# V2_3.net
KiCad netlist of a schematic drawn in Altium Designer
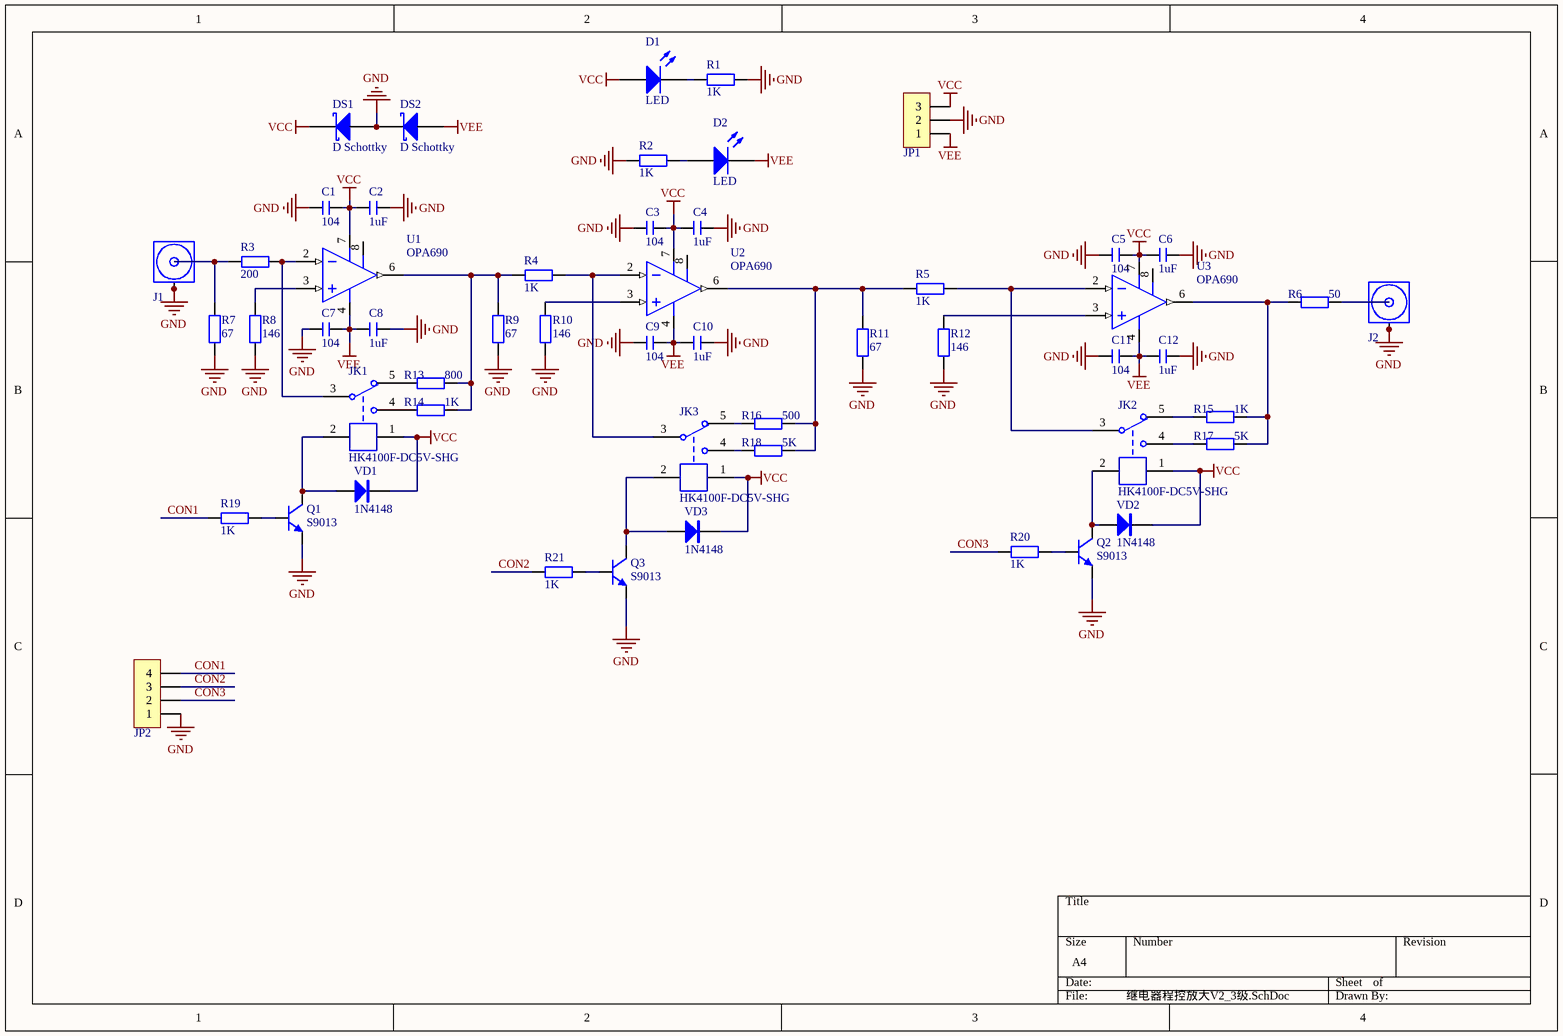
[diagram p0: 继电器程控放大V2_3级.SchDoc]

(export (version "E")
  (design (tool "Eeschema 10.0.6"))
  (components
    (comp (ref "C1")
      (value "104")
      (footprint "C 0603")
      (description "无极性贴片电容")
      (fields (field (name "版权归属") "源创客"))
      (libsource (lib "电阻-电容-电感") (part "C"))
    )
    (comp (ref "C2")
      (value "1uF")
      (footprint "C 0603")
      (description "无极性贴片电容")
      (fields (field (name "版权归属") "源创客"))
      (libsource (lib "电阻-电容-电感") (part "C"))
    )
    (comp (ref "C3")
      (value "104")
      (footprint "C 0603")
      (description "无极性贴片电容")
      (fields (field (name "版权归属") "源创客"))
      (libsource (lib "电阻-电容-电感") (part "C"))
    )
    (comp (ref "C4")
      (value "1uF")
      (footprint "C 0603")
      (description "无极性贴片电容")
      (fields (field (name "版权归属") "源创客"))
      (libsource (lib "电阻-电容-电感") (part "C"))
    )
    (comp (ref "C5")
      (value "104")
      (footprint "C 0603")
      (description "无极性贴片电容")
      (fields (field (name "版权归属") "源创客"))
      (libsource (lib "电阻-电容-电感") (part "C"))
    )
    (comp (ref "C6")
      (value "1uF")
      (footprint "C 0603")
      (description "无极性贴片电容")
      (fields (field (name "版权归属") "源创客"))
      (libsource (lib "电阻-电容-电感") (part "C"))
    )
    (comp (ref "C7")
      (value "104")
      (footprint "C 0603")
      (description "无极性贴片电容")
      (fields (field (name "版权归属") "源创客"))
      (libsource (lib "电阻-电容-电感") (part "C"))
    )
    (comp (ref "C8")
      (value "1uF")
      (footprint "C 0603")
      (description "无极性贴片电容")
      (fields (field (name "版权归属") "源创客"))
      (libsource (lib "电阻-电容-电感") (part "C"))
    )
    (comp (ref "C9")
      (value "104")
      (footprint "C 0603")
      (description "无极性贴片电容")
      (fields (field (name "版权归属") "源创客"))
      (libsource (lib "电阻-电容-电感") (part "C"))
    )
    (comp (ref "C10")
      (value "1uF")
      (footprint "C 0603")
      (description "无极性贴片电容")
      (fields (field (name "版权归属") "源创客"))
      (libsource (lib "电阻-电容-电感") (part "C"))
    )
    (comp (ref "C11")
      (value "104")
      (footprint "C 0603")
      (description "无极性贴片电容")
      (fields (field (name "版权归属") "源创客"))
      (libsource (lib "电阻-电容-电感") (part "C"))
    )
    (comp (ref "C12")
      (value "1uF")
      (footprint "C 0603")
      (description "无极性贴片电容")
      (fields (field (name "版权归属") "源创客"))
      (libsource (lib "电阻-电容-电感") (part "C"))
    )
    (comp (ref "D1")
      (value "LED")
      (footprint "LED_0805")
      (description "发光二极管")
      (fields (field (name "PUBLISHER") "Altium Limited"))
      (libsource (lib "LIB") (part "LED"))
    )
    (comp (ref "D2")
      (value "LED")
      (footprint "LED_0805")
      (description "发光二极管")
      (fields (field (name "PUBLISHER") "Altium Limited"))
      (libsource (lib "LIB") (part "LED"))
    )
    (comp (ref "DS1")
      (value "D Schottky")
      (footprint "DIODE-SMA")
      (description "Schottky Diode")
      (fields (field (name "PUBLISHER") "Altium Limited"))
      (libsource (lib "LIB") (part "D Schottky"))
    )
    (comp (ref "DS2")
      (value "D Schottky")
      (footprint "DIODE-SMA")
      (description "Schottky Diode")
      (fields (field (name "PUBLISHER") "Altium Limited"))
      (libsource (lib "LIB") (part "D Schottky"))
    )
    (comp (ref "J1") (value "COAX") (footprint "MCX5.08-5-H") (libsource (lib "LIB") (part "COAX")))
    (comp (ref "J2") (value "COAX") (footprint "MCX5.08-5-H") (libsource (lib "LIB") (part "COAX")))
    (comp (ref "JK1")
      (value "HK4100F-DC5V-SHG")
      (footprint "HK4100F")
      (description "单路双控继电器")
      (fields (field (name "版权归属") "源创客"))
      (libsource (lib "继电器") (part "HK4100F"))
    )
    (comp (ref "JK2")
      (value "HK4100F-DC5V-SHG")
      (footprint "HK4100F")
      (description "单路双控继电器")
      (fields (field (name "版权归属") "源创客"))
      (libsource (lib "继电器") (part "HK4100F"))
    )
    (comp (ref "JK3")
      (value "HK4100F-DC5V-SHG")
      (footprint "HK4100F")
      (description "单路双控继电器")
      (fields (field (name "版权归属") "源创客"))
      (libsource (lib "继电器") (part "HK4100F"))
    )
    (comp (ref "JP1")
      (value "HDR-1X3")
      (footprint "XH2.54-3P_H")
      (description "3P接插件")
      (fields (field (name "版权归属") "源创客"))
      (libsource (lib "接插件") (part "Header 3"))
    )
    (comp (ref "JP2")
      (value "HDR-1X4")
      (footprint "HDR-1X4")
      (description "4P接插件")
      (fields (field (name "版权归属") "源创客"))
      (libsource (lib "接插件") (part "Header 4"))
    )
    (comp (ref "Q1")
      (value "S9013")
      (footprint "SOT23-3N")
      (description "低频放大-NPN型")
      (fields (field (name "版权归属") "源创客"))
      (libsource (lib "三极管") (part "9013-SMD"))
    )
    (comp (ref "Q2")
      (value "S9013")
      (footprint "SOT23-3N")
      (description "低频放大-NPN型")
      (fields (field (name "版权归属") "源创客"))
      (libsource (lib "三极管") (part "9013-SMD"))
    )
    (comp (ref "Q3")
      (value "S9013")
      (footprint "SOT23-3N")
      (description "低频放大-NPN型")
      (fields (field (name "版权归属") "源创客"))
      (libsource (lib "三极管") (part "9013-SMD"))
    )
    (comp (ref "R1")
      (value "1K")
      (footprint "R 0805")
      (description "贴片电阻")
      (fields (field (name "版权归属") "源创客"))
      (libsource (lib "电阻-电容-电感") (part "R"))
    )
    (comp (ref "R2")
      (value "1K")
      (footprint "R 0805")
      (description "贴片电阻")
      (fields (field (name "版权归属") "源创客"))
      (libsource (lib "电阻-电容-电感") (part "R"))
    )
    (comp (ref "R3")
      (value "200")
      (footprint "R 0603")
      (description "贴片电阻")
      (fields (field (name "版权归属") "源创客"))
      (libsource (lib "电阻-电容-电感") (part "R"))
    )
    (comp (ref "R4")
      (value "1K")
      (footprint "R 0603")
      (description "贴片电阻")
      (fields (field (name "版权归属") "源创客"))
      (libsource (lib "电阻-电容-电感") (part "R"))
    )
    (comp (ref "R5")
      (value "1K")
      (footprint "R 0603")
      (description "贴片电阻")
      (fields (field (name "版权归属") "源创客"))
      (libsource (lib "电阻-电容-电感") (part "R"))
    )
    (comp (ref "R6")
      (value "50")
      (footprint "R 0603")
      (description "贴片电阻")
      (fields (field (name "版权归属") "源创客"))
      (libsource (lib "电阻-电容-电感") (part "R"))
    )
    (comp (ref "R7")
      (value "67")
      (footprint "R 0603")
      (description "贴片电阻")
      (fields (field (name "版权归属") "源创客"))
      (libsource (lib "电阻-电容-电感") (part "R"))
    )
    (comp (ref "R8")
      (value "146")
      (footprint "R 0603")
      (description "贴片电阻")
      (fields (field (name "版权归属") "源创客"))
      (libsource (lib "电阻-电容-电感") (part "R"))
    )
    (comp (ref "R9")
      (value "67")
      (footprint "R 0603")
      (description "贴片电阻")
      (fields (field (name "版权归属") "源创客"))
      (libsource (lib "电阻-电容-电感") (part "R"))
    )
    (comp (ref "R10")
      (value "146")
      (footprint "R 0603")
      (description "贴片电阻")
      (fields (field (name "版权归属") "源创客"))
      (libsource (lib "电阻-电容-电感") (part "R"))
    )
    (comp (ref "R11")
      (value "67")
      (footprint "R 0603")
      (description "贴片电阻")
      (fields (field (name "版权归属") "源创客"))
      (libsource (lib "电阻-电容-电感") (part "R"))
    )
    (comp (ref "R12")
      (value "146")
      (footprint "R 0603")
      (description "贴片电阻")
      (fields (field (name "版权归属") "源创客"))
      (libsource (lib "电阻-电容-电感") (part "R"))
    )
    (comp (ref "R13")
      (value "800")
      (footprint "R 0603")
      (description "贴片电阻")
      (fields (field (name "版权归属") "源创客"))
      (libsource (lib "电阻-电容-电感") (part "R"))
    )
    (comp (ref "R14")
      (value "1K")
      (footprint "R 0603")
      (description "贴片电阻")
      (fields (field (name "版权归属") "源创客"))
      (libsource (lib "电阻-电容-电感") (part "R"))
    )
    (comp (ref "R15")
      (value "1K")
      (footprint "R 0603")
      (description "贴片电阻")
      (fields (field (name "版权归属") "源创客"))
      (libsource (lib "电阻-电容-电感") (part "R"))
    )
    (comp (ref "R16")
      (value "500")
      (footprint "R 0603")
      (description "贴片电阻")
      (fields (field (name "版权归属") "源创客"))
      (libsource (lib "电阻-电容-电感") (part "R"))
    )
    (comp (ref "R17")
      (value "5K")
      (footprint "R 0603")
      (description "贴片电阻")
      (fields (field (name "版权归属") "源创客"))
      (libsource (lib "电阻-电容-电感") (part "R"))
    )
    (comp (ref "R18")
      (value "5K")
      (footprint "R 0603")
      (description "贴片电阻")
      (fields (field (name "版权归属") "源创客"))
      (libsource (lib "电阻-电容-电感") (part "R"))
    )
    (comp (ref "R19")
      (value "1K")
      (footprint "R 0603")
      (description "贴片电阻")
      (fields (field (name "版权归属") "源创客"))
      (libsource (lib "电阻-电容-电感") (part "R"))
    )
    (comp (ref "R20")
      (value "1K")
      (footprint "R 0603")
      (description "贴片电阻")
      (fields (field (name "版权归属") "源创客"))
      (libsource (lib "电阻-电容-电感") (part "R"))
    )
    (comp (ref "R21")
      (value "1K")
      (footprint "R 0603")
      (description "贴片电阻")
      (fields (field (name "版权归属") "源创客"))
      (libsource (lib "电阻-电容-电感") (part "R"))
    )
    (comp (ref "U1")
      (value "OPA690")
      (footprint "LIB:SOIC8_N")
      (description "具有禁用功能的宽带电压反馈运算放大器")
      (libsource (lib "LIB") (part "OPA690ID"))
    )
    (comp (ref "U2")
      (value "OPA690")
      (footprint "LIB:SOIC8_N")
      (description "具有禁用功能的宽带电压反馈运算放大器")
      (libsource (lib "LIB") (part "OPA690ID"))
    )
    (comp (ref "U3")
      (value "OPA690")
      (footprint "LIB:SOIC8_N")
      (description "具有禁用功能的宽带电压反馈运算放大器")
      (libsource (lib "LIB") (part "OPA690ID"))
    )
    (comp (ref "VD1")
      (value "1N4148")
      (footprint "SOD-323")
      (description "高速开关二极管")
      (fields (field (name "版权归属") "源创客"))
      (libsource (lib "二极管-整流桥") (part "1N4148"))
    )
    (comp (ref "VD2")
      (value "1N4148")
      (footprint "SOD-323")
      (description "高速开关二极管")
      (fields (field (name "版权归属") "源创客"))
      (libsource (lib "二极管-整流桥") (part "1N4148"))
    )
    (comp (ref "VD3")
      (value "1N4148")
      (footprint "SOD-323")
      (description "高速开关二极管")
      (fields (field (name "版权归属") "源创客"))
      (libsource (lib "二极管-整流桥") (part "1N4148"))
    )
  )
  (nets
    (net (code "1") (name "/CON1") (class "Default")
      (node (ref "JP2") (pin "4") (pinfunction "4_4") (pintype "passive"))
      (node (ref "R19") (pin "1") (pinfunction "1_1") (pintype "passive"))
    )
    (net (code "2") (name "/CON2") (class "Default")
      (node (ref "JP2") (pin "3") (pinfunction "3_3") (pintype "passive"))
      (node (ref "R21") (pin "1") (pinfunction "1_1") (pintype "passive"))
    )
    (net (code "3") (name "/CON3") (class "Default")
      (node (ref "JP2") (pin "2") (pinfunction "2_2") (pintype "passive"))
      (node (ref "R20") (pin "1") (pinfunction "1_1") (pintype "passive"))
    )
    (net (code "4") (name "GND") (class "Default")
      (node (ref "C1") (pin "1") (pinfunction "1_1") (pintype "passive"))
      (node (ref "C10") (pin "2") (pinfunction "2_2") (pintype "passive"))
      (node (ref "C11") (pin "1") (pinfunction "1_1") (pintype "passive"))
      (node (ref "C12") (pin "2") (pinfunction "2_2") (pintype "passive"))
      (node (ref "C2") (pin "2") (pinfunction "2_2") (pintype "passive"))
      (node (ref "C3") (pin "1") (pinfunction "1_1") (pintype "passive"))
      (node (ref "C4") (pin "2") (pinfunction "2_2") (pintype "passive"))
      (node (ref "C5") (pin "1") (pinfunction "1_1") (pintype "passive"))
      (node (ref "C6") (pin "2") (pinfunction "2_2") (pintype "passive"))
      (node (ref "C7") (pin "1") (pinfunction "1_1") (pintype "passive"))
      (node (ref "C8") (pin "2") (pinfunction "2_2") (pintype "passive"))
      (node (ref "C9") (pin "1") (pinfunction "1_1") (pintype "passive"))
      (node (ref "DS1") (pin "1") (pinfunction "1_1") (pintype "passive"))
      (node (ref "DS2") (pin "2") (pinfunction "2_2") (pintype "passive"))
      (node (ref "J1") (pin "2") (pinfunction "GND_2") (pintype "passive"))
      (node (ref "J1") (pin "3") (pinfunction "GND_3") (pintype "passive"))
      (node (ref "J1") (pin "4") (pinfunction "GND_4") (pintype "passive"))
      (node (ref "J1") (pin "5") (pinfunction "GND_5") (pintype "passive"))
      (node (ref "J2") (pin "2") (pinfunction "GND_2") (pintype "passive"))
      (node (ref "J2") (pin "3") (pinfunction "GND_3") (pintype "passive"))
      (node (ref "J2") (pin "4") (pinfunction "GND_4") (pintype "passive"))
      (node (ref "J2") (pin "5") (pinfunction "GND_5") (pintype "passive"))
      (node (ref "JP1") (pin "2") (pinfunction "2_2") (pintype "passive"))
      (node (ref "JP2") (pin "1") (pinfunction "1_1") (pintype "passive"))
      (node (ref "Q1") (pin "2") (pinfunction "E_2") (pintype "passive"))
      (node (ref "Q2") (pin "2") (pinfunction "E_2") (pintype "passive"))
      (node (ref "Q3") (pin "2") (pinfunction "E_2") (pintype "passive"))
      (node (ref "R1") (pin "2") (pinfunction "2_2") (pintype "passive"))
      (node (ref "R10") (pin "2") (pinfunction "2_2") (pintype "passive"))
      (node (ref "R11") (pin "2") (pinfunction "2_2") (pintype "passive"))
      (node (ref "R12") (pin "2") (pinfunction "2_2") (pintype "passive"))
      (node (ref "R2") (pin "1") (pinfunction "1_1") (pintype "passive"))
      (node (ref "R7") (pin "2") (pinfunction "2_2") (pintype "passive"))
      (node (ref "R8") (pin "1") (pinfunction "1_1") (pintype "passive"))
      (node (ref "R9") (pin "2") (pinfunction "2_2") (pintype "passive"))
    )
    (net (code "5") (name "Net-(D1-K)") (class "Default")
      (node (ref "D1") (pin "2") (pinfunction "K_2") (pintype "passive"))
      (node (ref "R1") (pin "1") (pinfunction "1_1") (pintype "passive"))
    )
    (net (code "6") (name "Net-(D2-A)") (class "Default")
      (node (ref "D2") (pin "1") (pinfunction "A_1") (pintype "passive"))
      (node (ref "R2") (pin "2") (pinfunction "2_2") (pintype "passive"))
    )
    (net (code "7") (name "Net-(J1-Signal)") (class "Default")
      (node (ref "J1") (pin "1") (pinfunction "Signal_1") (pintype "passive"))
      (node (ref "R3") (pin "2") (pinfunction "2_2") (pintype "passive"))
      (node (ref "R7") (pin "1") (pinfunction "1_1") (pintype "passive"))
    )
    (net (code "8") (name "Net-(J2-Signal)") (class "Default")
      (node (ref "J2") (pin "1") (pinfunction "Signal_1") (pintype "passive"))
      (node (ref "R6") (pin "1") (pinfunction "1_1") (pintype "passive"))
    )
    (net (code "9") (name "Net-(JK1-Pad4)") (class "Default")
      (node (ref "JK1") (pin "4") (pinfunction "4_4") (pintype "passive"))
      (node (ref "R14") (pin "1") (pinfunction "1_1") (pintype "passive"))
    )
    (net (code "10") (name "Net-(JK1-Pad5)") (class "Default")
      (node (ref "JK1") (pin "5") (pinfunction "5_5") (pintype "passive"))
      (node (ref "R13") (pin "1") (pinfunction "1_1") (pintype "passive"))
    )
    (net (code "11") (name "Net-(JK2-Pad4)") (class "Default")
      (node (ref "JK2") (pin "4") (pinfunction "4_4") (pintype "passive"))
      (node (ref "R17") (pin "2") (pinfunction "2_2") (pintype "passive"))
    )
    (net (code "12") (name "Net-(JK2-Pad5)") (class "Default")
      (node (ref "JK2") (pin "5") (pinfunction "5_5") (pintype "passive"))
      (node (ref "R15") (pin "2") (pinfunction "2_2") (pintype "passive"))
    )
    (net (code "13") (name "Net-(JK3-Pad4)") (class "Default")
      (node (ref "JK3") (pin "4") (pinfunction "4_4") (pintype "passive"))
      (node (ref "R18") (pin "2") (pinfunction "2_2") (pintype "passive"))
    )
    (net (code "14") (name "Net-(JK3-Pad5)") (class "Default")
      (node (ref "JK3") (pin "5") (pinfunction "5_5") (pintype "passive"))
      (node (ref "R16") (pin "2") (pinfunction "2_2") (pintype "passive"))
    )
    (net (code "15") (name "Net-(Q1-B)") (class "Default")
      (node (ref "Q1") (pin "1") (pinfunction "B_1") (pintype "passive"))
      (node (ref "R19") (pin "2") (pinfunction "2_2") (pintype "passive"))
    )
    (net (code "16") (name "Net-(Q1-C)") (class "Default")
      (node (ref "JK1") (pin "2") (pinfunction "2_2") (pintype "passive"))
      (node (ref "Q1") (pin "3") (pinfunction "C_3") (pintype "passive"))
      (node (ref "VD1") (pin "1") (pinfunction "A_1") (pintype "passive"))
    )
    (net (code "17") (name "Net-(Q2-B)") (class "Default")
      (node (ref "Q2") (pin "1") (pinfunction "B_1") (pintype "passive"))
      (node (ref "R20") (pin "2") (pinfunction "2_2") (pintype "passive"))
    )
    (net (code "18") (name "Net-(Q2-C)") (class "Default")
      (node (ref "JK2") (pin "2") (pinfunction "2_2") (pintype "passive"))
      (node (ref "Q2") (pin "3") (pinfunction "C_3") (pintype "passive"))
      (node (ref "VD2") (pin "1") (pinfunction "A_1") (pintype "passive"))
    )
    (net (code "19") (name "Net-(Q3-B)") (class "Default")
      (node (ref "Q3") (pin "1") (pinfunction "B_1") (pintype "passive"))
      (node (ref "R21") (pin "2") (pinfunction "2_2") (pintype "passive"))
    )
    (net (code "20") (name "Net-(Q3-C)") (class "Default")
      (node (ref "JK3") (pin "2") (pinfunction "2_2") (pintype "passive"))
      (node (ref "Q3") (pin "3") (pinfunction "C_3") (pintype "passive"))
      (node (ref "VD3") (pin "1") (pinfunction "A_1") (pintype "passive"))
    )
    (net (code "21") (name "Net-(U1-IN+)") (class "Default")
      (node (ref "R8") (pin "2") (pinfunction "2_2") (pintype "passive"))
      (node (ref "U1") (pin "3") (pinfunction "IN+_3") (pintype "input"))
    )
    (net (code "22") (name "Net-(U1-IN-)") (class "Default")
      (node (ref "JK1") (pin "3") (pinfunction "3_3") (pintype "passive"))
      (node (ref "R3") (pin "1") (pinfunction "1_1") (pintype "passive"))
      (node (ref "U1") (pin "2") (pinfunction "IN-_2") (pintype "input"))
    )
    (net (code "23") (name "Net-(U1-OUT)") (class "Default")
      (node (ref "R13") (pin "2") (pinfunction "2_2") (pintype "passive"))
      (node (ref "R14") (pin "2") (pinfunction "2_2") (pintype "passive"))
      (node (ref "R4") (pin "2") (pinfunction "2_2") (pintype "passive"))
      (node (ref "R9") (pin "1") (pinfunction "1_1") (pintype "passive"))
      (node (ref "U1") (pin "6") (pinfunction "OUT_6") (pintype "output"))
    )
    (net (code "24") (name "Net-(U2-IN+)") (class "Default")
      (node (ref "R10") (pin "1") (pinfunction "1_1") (pintype "passive"))
      (node (ref "U2") (pin "3") (pinfunction "IN+_3") (pintype "input"))
    )
    (net (code "25") (name "Net-(U2-IN-)") (class "Default")
      (node (ref "JK3") (pin "3") (pinfunction "3_3") (pintype "passive"))
      (node (ref "R4") (pin "1") (pinfunction "1_1") (pintype "passive"))
      (node (ref "U2") (pin "2") (pinfunction "IN-_2") (pintype "input"))
    )
    (net (code "26") (name "Net-(U2-OUT)") (class "Default")
      (node (ref "R11") (pin "1") (pinfunction "1_1") (pintype "passive"))
      (node (ref "R16") (pin "1") (pinfunction "1_1") (pintype "passive"))
      (node (ref "R18") (pin "1") (pinfunction "1_1") (pintype "passive"))
      (node (ref "R5") (pin "2") (pinfunction "2_2") (pintype "passive"))
      (node (ref "U2") (pin "6") (pinfunction "OUT_6") (pintype "output"))
    )
    (net (code "27") (name "Net-(U3-IN+)") (class "Default")
      (node (ref "R12") (pin "1") (pinfunction "1_1") (pintype "passive"))
      (node (ref "U3") (pin "3") (pinfunction "IN+_3") (pintype "input"))
    )
    (net (code "28") (name "Net-(U3-IN-)") (class "Default")
      (node (ref "JK2") (pin "3") (pinfunction "3_3") (pintype "passive"))
      (node (ref "R5") (pin "1") (pinfunction "1_1") (pintype "passive"))
      (node (ref "U3") (pin "2") (pinfunction "IN-_2") (pintype "input"))
    )
    (net (code "29") (name "Net-(U3-OUT)") (class "Default")
      (node (ref "R15") (pin "1") (pinfunction "1_1") (pintype "passive"))
      (node (ref "R17") (pin "1") (pinfunction "1_1") (pintype "passive"))
      (node (ref "R6") (pin "2") (pinfunction "2_2") (pintype "passive"))
      (node (ref "U3") (pin "6") (pinfunction "OUT_6") (pintype "output"))
    )
    (net (code "30") (name "VCC") (class "Default")
      (node (ref "C1") (pin "2") (pinfunction "2_2") (pintype "passive"))
      (node (ref "C2") (pin "1") (pinfunction "1_1") (pintype "passive"))
      (node (ref "C3") (pin "2") (pinfunction "2_2") (pintype "passive"))
      (node (ref "C4") (pin "1") (pinfunction "1_1") (pintype "passive"))
      (node (ref "C5") (pin "2") (pinfunction "2_2") (pintype "passive"))
      (node (ref "C6") (pin "1") (pinfunction "1_1") (pintype "passive"))
      (node (ref "D1") (pin "1") (pinfunction "A_1") (pintype "passive"))
      (node (ref "DS1") (pin "2") (pinfunction "2_2") (pintype "passive"))
      (node (ref "JK1") (pin "1") (pinfunction "1_1") (pintype "passive"))
      (node (ref "JK2") (pin "1") (pinfunction "1_1") (pintype "passive"))
      (node (ref "JK3") (pin "1") (pinfunction "1_1") (pintype "passive"))
      (node (ref "JP1") (pin "3") (pinfunction "3_3") (pintype "passive"))
      (node (ref "U1") (pin "7") (pinfunction "V+_7") (pintype "power_in"))
      (node (ref "U2") (pin "7") (pinfunction "V+_7") (pintype "power_in"))
      (node (ref "U3") (pin "7") (pinfunction "V+_7") (pintype "power_in"))
      (node (ref "VD1") (pin "2") (pinfunction "K_2") (pintype "passive"))
      (node (ref "VD2") (pin "2") (pinfunction "K_2") (pintype "passive"))
      (node (ref "VD3") (pin "2") (pinfunction "K_2") (pintype "passive"))
    )
    (net (code "31") (name "VEE") (class "Default")
      (node (ref "C10") (pin "1") (pinfunction "1_1") (pintype "passive"))
      (node (ref "C11") (pin "2") (pinfunction "2_2") (pintype "passive"))
      (node (ref "C12") (pin "1") (pinfunction "1_1") (pintype "passive"))
      (node (ref "C7") (pin "2") (pinfunction "2_2") (pintype "passive"))
      (node (ref "C8") (pin "1") (pinfunction "1_1") (pintype "passive"))
      (node (ref "C9") (pin "2") (pinfunction "2_2") (pintype "passive"))
      (node (ref "D2") (pin "2") (pinfunction "K_2") (pintype "passive"))
      (node (ref "DS2") (pin "1") (pinfunction "1_1") (pintype "passive"))
      (node (ref "JP1") (pin "1") (pinfunction "1_1") (pintype "passive"))
      (node (ref "U1") (pin "4") (pinfunction "V-_4") (pintype "power_in"))
      (node (ref "U2") (pin "4") (pinfunction "V-_4") (pintype "power_in"))
      (node (ref "U3") (pin "4") (pinfunction "V-_4") (pintype "power_in"))
    )
    (net (code "32") (name "unconnected-(U1-DIS-Pad8)") (class "Default")
      (node (ref "U1") (pin "8") (pinfunction "DIS_8") (pintype "passive"))
    )
    (net (code "33") (name "unconnected-(U2-DIS-Pad8)") (class "Default")
      (node (ref "U2") (pin "8") (pinfunction "DIS_8") (pintype "passive"))
    )
    (net (code "34") (name "unconnected-(U3-DIS-Pad8)") (class "Default")
      (node (ref "U3") (pin "8") (pinfunction "DIS_8") (pintype "passive"))
    )
  )
)
